# Mabee_CO2_v1_1.net
KiCad netlist of a schematic drawn in EAGLE
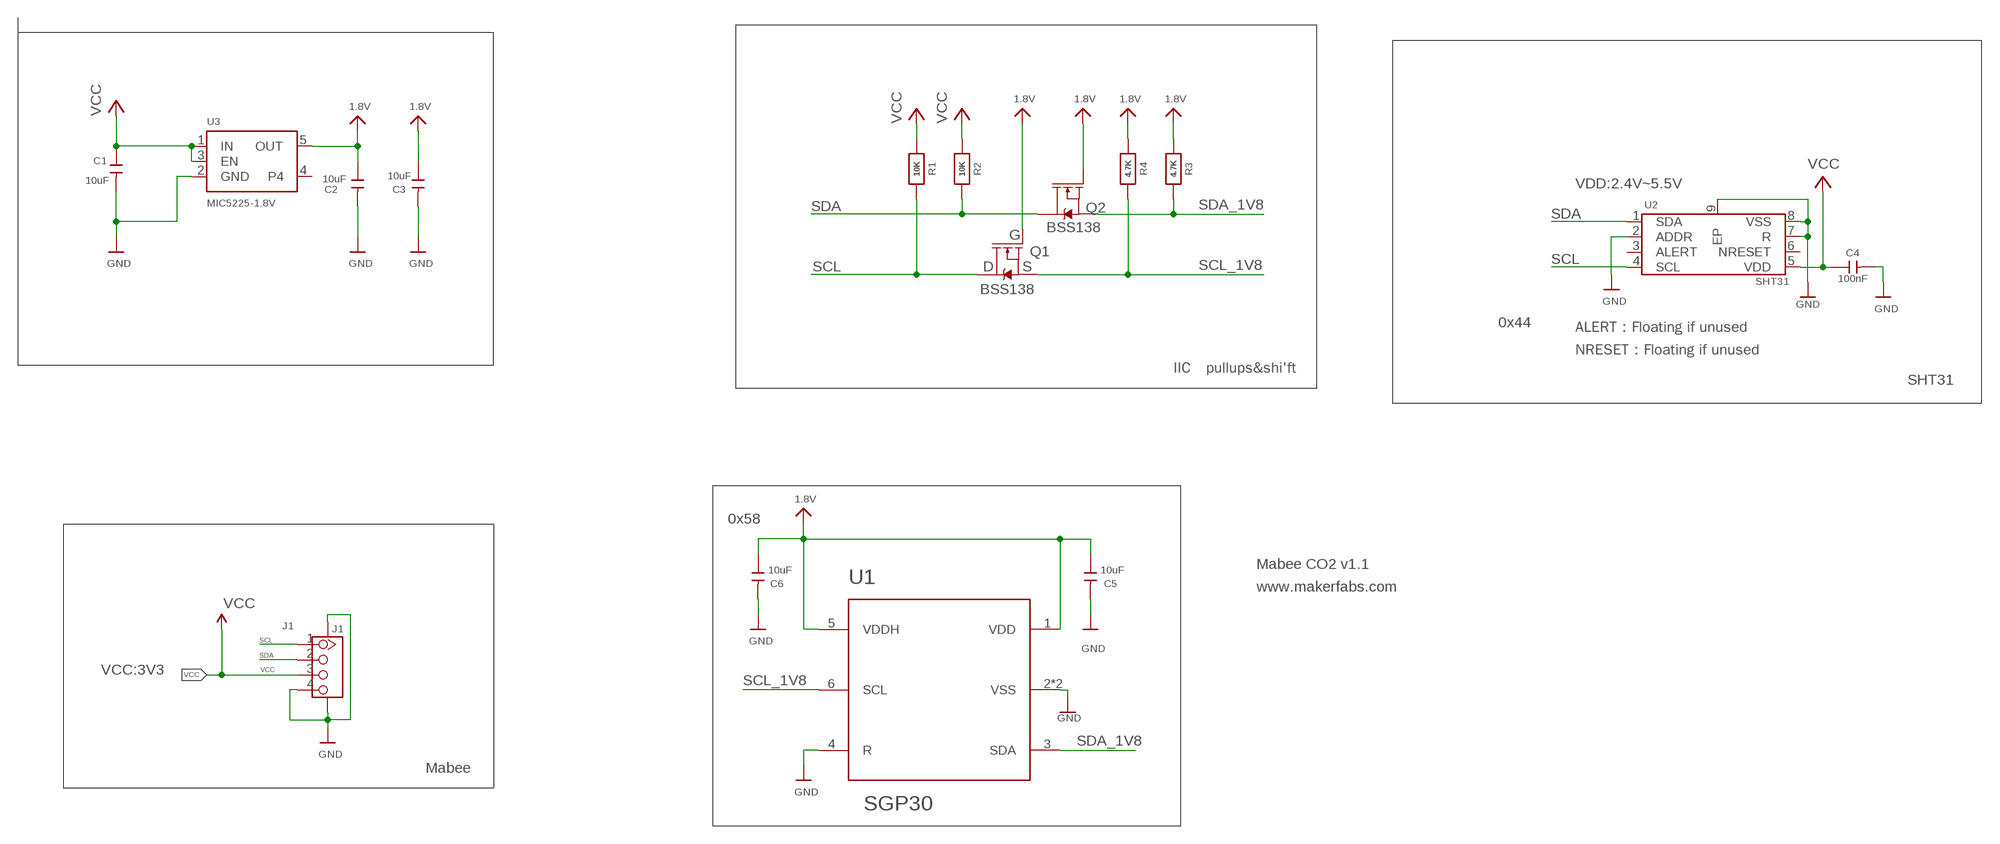
[diagram p0: schematic, sheet 1]

(export (version "E")
  (design (tool "Eeschema 10.0.6"))
  (components
    (comp (ref "C1")
      (value "10uF")
      (footprint "eagle-import:0603")
      (libsource (lib "eagle-import") (part "C-0603"))
    )
    (comp (ref "C2")
      (value "10uF")
      (footprint "eagle-import:0603")
      (libsource (lib "eagle-import") (part "C-0603"))
    )
    (comp (ref "C3")
      (value "10uF")
      (footprint "eagle-import:0603")
      (libsource (lib "eagle-import") (part "C-0603"))
    )
    (comp (ref "C4")
      (value "100nF")
      (footprint "eagle-import:0603")
      (libsource (lib "eagle-import") (part "C-0603"))
    )
    (comp (ref "C5")
      (value "10uF")
      (footprint "eagle-import:0603")
      (libsource (lib "eagle-import") (part "C-0603"))
    )
    (comp (ref "C6")
      (value "10uF")
      (footprint "eagle-import:0603")
      (libsource (lib "eagle-import") (part "C-0603"))
    )
    (comp (ref "J1")
      (value "J1")
      (footprint "eagle-import:HW4-SMD-2.0-90D")
      (libsource (lib "eagle-import") (part "GROVE-CONNECTOR-SMD'90D'"))
    )
    (comp (ref "Q1")
      (value "BSS138")
      (footprint "eagle-import:SOT23-3")
      (libsource (lib "eagle-import") (part "MOSFET-NCH-BSS138"))
    )
    (comp (ref "Q2")
      (value "BSS138")
      (footprint "eagle-import:SOT23-3")
      (fields (field (name "PROD_ID") "TRANS-00830"))
      (libsource (lib "eagle-import") (part "MOSFET-NCH-BSS138"))
    )
    (comp (ref "R1")
      (value "10K")
      (footprint "eagle-import:0603-NO")
      (libsource (lib "eagle-import") (part "RESISTOR_0603_NOOUT"))
    )
    (comp (ref "R2")
      (value "10K")
      (footprint "eagle-import:0603-NO")
      (libsource (lib "eagle-import") (part "RESISTOR_0603_NOOUT"))
    )
    (comp (ref "R3")
      (value "4.7K")
      (footprint "eagle-import:0603-NO")
      (libsource (lib "eagle-import") (part "RESISTOR_0603_NOOUT"))
    )
    (comp (ref "R4")
      (value "4.7K")
      (footprint "eagle-import:0603-NO")
      (libsource (lib "eagle-import") (part "RESISTOR_0603_NOOUT"))
    )
    (comp (ref "U1")
      (value "SGP30")
      (footprint "eagle-import:SGP30")
      (libsource (lib "eagle-import") (part "SGP30"))
    )
    (comp (ref "U2")
      (value "SHT31")
      (footprint "eagle-import:DFN-8(3X3)_EP")
      (libsource (lib "eagle-import") (part "SHT31"))
    )
    (comp (ref "U3")
      (value "MIC5225-1.8V")
      (footprint "eagle-import:SOT23-5")
      (libsource (lib "eagle-import") (part "VREG_SOT23-5"))
    )
  )
  (nets
    (net (code "1") (name "/SCL") (class "Default")
      (node (ref "J1") (pin "1") (pinfunction "1_1") (pintype "bidirectional"))
      (node (ref "Q1") (pin "3") (pinfunction "D_3") (pintype "bidirectional"))
      (node (ref "R1") (pin "2") (pinfunction "2_2") (pintype "passive"))
      (node (ref "U2") (pin "4") (pinfunction "SCL_4") (pintype "bidirectional"))
    )
    (net (code "2") (name "/SCL_1V8") (class "Default")
      (node (ref "Q1") (pin "2") (pinfunction "S_2") (pintype "bidirectional"))
      (node (ref "R4") (pin "2") (pinfunction "2_2") (pintype "passive"))
      (node (ref "U1") (pin "6") (pinfunction "SCL_6") (pintype "bidirectional"))
    )
    (net (code "3") (name "/SDA") (class "Default")
      (node (ref "J1") (pin "2") (pinfunction "2_2") (pintype "bidirectional"))
      (node (ref "Q2") (pin "3") (pinfunction "D_3") (pintype "bidirectional"))
      (node (ref "R2") (pin "2") (pinfunction "2_2") (pintype "passive"))
      (node (ref "U2") (pin "1") (pinfunction "SDA_1") (pintype "bidirectional"))
    )
    (net (code "4") (name "/SDA_1V8") (class "Default")
      (node (ref "Q2") (pin "2") (pinfunction "S_2") (pintype "bidirectional"))
      (node (ref "R3") (pin "2") (pinfunction "2_2") (pintype "passive"))
      (node (ref "U1") (pin "3") (pinfunction "SDA_3") (pintype "bidirectional"))
    )
    (net (code "5") (name "1.8V") (class "Default")
      (node (ref "C2") (pin "1") (pinfunction "1_1") (pintype "passive"))
      (node (ref "C3") (pin "1") (pinfunction "1_1") (pintype "passive"))
      (node (ref "C5") (pin "1") (pinfunction "1_1") (pintype "passive"))
      (node (ref "C6") (pin "1") (pinfunction "1_1") (pintype "passive"))
      (node (ref "Q1") (pin "1") (pinfunction "G_1") (pintype "bidirectional"))
      (node (ref "Q2") (pin "1") (pinfunction "G_1") (pintype "bidirectional"))
      (node (ref "R3") (pin "1") (pinfunction "1_1") (pintype "passive"))
      (node (ref "R4") (pin "1") (pinfunction "1_1") (pintype "passive"))
      (node (ref "U1") (pin "1") (pinfunction "VDD_1") (pintype "bidirectional"))
      (node (ref "U1") (pin "5") (pinfunction "VDDH_5") (pintype "bidirectional"))
      (node (ref "U3") (pin "5") (pinfunction "OUT_5") (pintype "power_in"))
    )
    (net (code "6") (name "GND") (class "Default")
      (node (ref "C1") (pin "2") (pinfunction "2_2") (pintype "passive"))
      (node (ref "C2") (pin "2") (pinfunction "2_2") (pintype "passive"))
      (node (ref "C3") (pin "2") (pinfunction "2_2") (pintype "passive"))
      (node (ref "C4") (pin "2") (pinfunction "2_2") (pintype "passive"))
      (node (ref "C5") (pin "2") (pinfunction "2_2") (pintype "passive"))
      (node (ref "C6") (pin "2") (pinfunction "2_2") (pintype "passive"))
      (node (ref "J1") (pin "4") (pinfunction "4_4") (pintype "bidirectional"))
      (node (ref "J1") (pin "SS1") (pinfunction "SS1_SS1") (pintype "bidirectional"))
      (node (ref "J1") (pin "SS2") (pinfunction "SS2_SS2") (pintype "bidirectional"))
      (node (ref "U1") (pin "2") (pinfunction "VSS_2") (pintype "bidirectional"))
      (node (ref "U1") (pin "4") (pinfunction "R_4") (pintype "bidirectional"))
      (node (ref "U1") (pin "P$7") (pinfunction "VSS_P$7") (pintype "bidirectional"))
      (node (ref "U2") (pin "2") (pinfunction "ADDR_2") (pintype "bidirectional"))
      (node (ref "U2") (pin "7") (pinfunction "R_7") (pintype "bidirectional"))
      (node (ref "U2") (pin "8") (pinfunction "VSS_8") (pintype "bidirectional"))
      (node (ref "U2") (pin "9") (pinfunction "EP_9") (pintype "bidirectional"))
      (node (ref "U3") (pin "2") (pinfunction "GND_2") (pintype "power_in"))
    )
    (net (code "7") (name "VCC") (class "Default")
      (node (ref "C1") (pin "1") (pinfunction "1_1") (pintype "passive"))
      (node (ref "C4") (pin "1") (pinfunction "1_1") (pintype "passive"))
      (node (ref "J1") (pin "3") (pinfunction "3_3") (pintype "bidirectional"))
      (node (ref "R1") (pin "1") (pinfunction "1_1") (pintype "passive"))
      (node (ref "R2") (pin "1") (pinfunction "1_1") (pintype "passive"))
      (node (ref "U2") (pin "5") (pinfunction "VDD_5") (pintype "bidirectional"))
      (node (ref "U3") (pin "1") (pinfunction "IN_1") (pintype "power_in"))
      (node (ref "U3") (pin "3") (pinfunction "EN_3") (pintype "input"))
    )
    (net (code "8") (name "unconnected-(U2-ALERT-Pad3)") (class "Default")
      (node (ref "U2") (pin "3") (pinfunction "ALERT_3") (pintype "bidirectional"))
    )
    (net (code "9") (name "unconnected-(U2-NRESET-Pad6)") (class "Default")
      (node (ref "U2") (pin "6") (pinfunction "NRESET_6") (pintype "bidirectional"))
    )
    (net (code "10") (name "unconnected-(U3-P4-Pad4)") (class "Default")
      (node (ref "U3") (pin "4") (pinfunction "P4_4") (pintype "bidirectional"))
    )
  )
)
